# Seeed_XIAO_nRF52840_v1_0.net
KiCad netlist of a schematic drawn in EAGLE
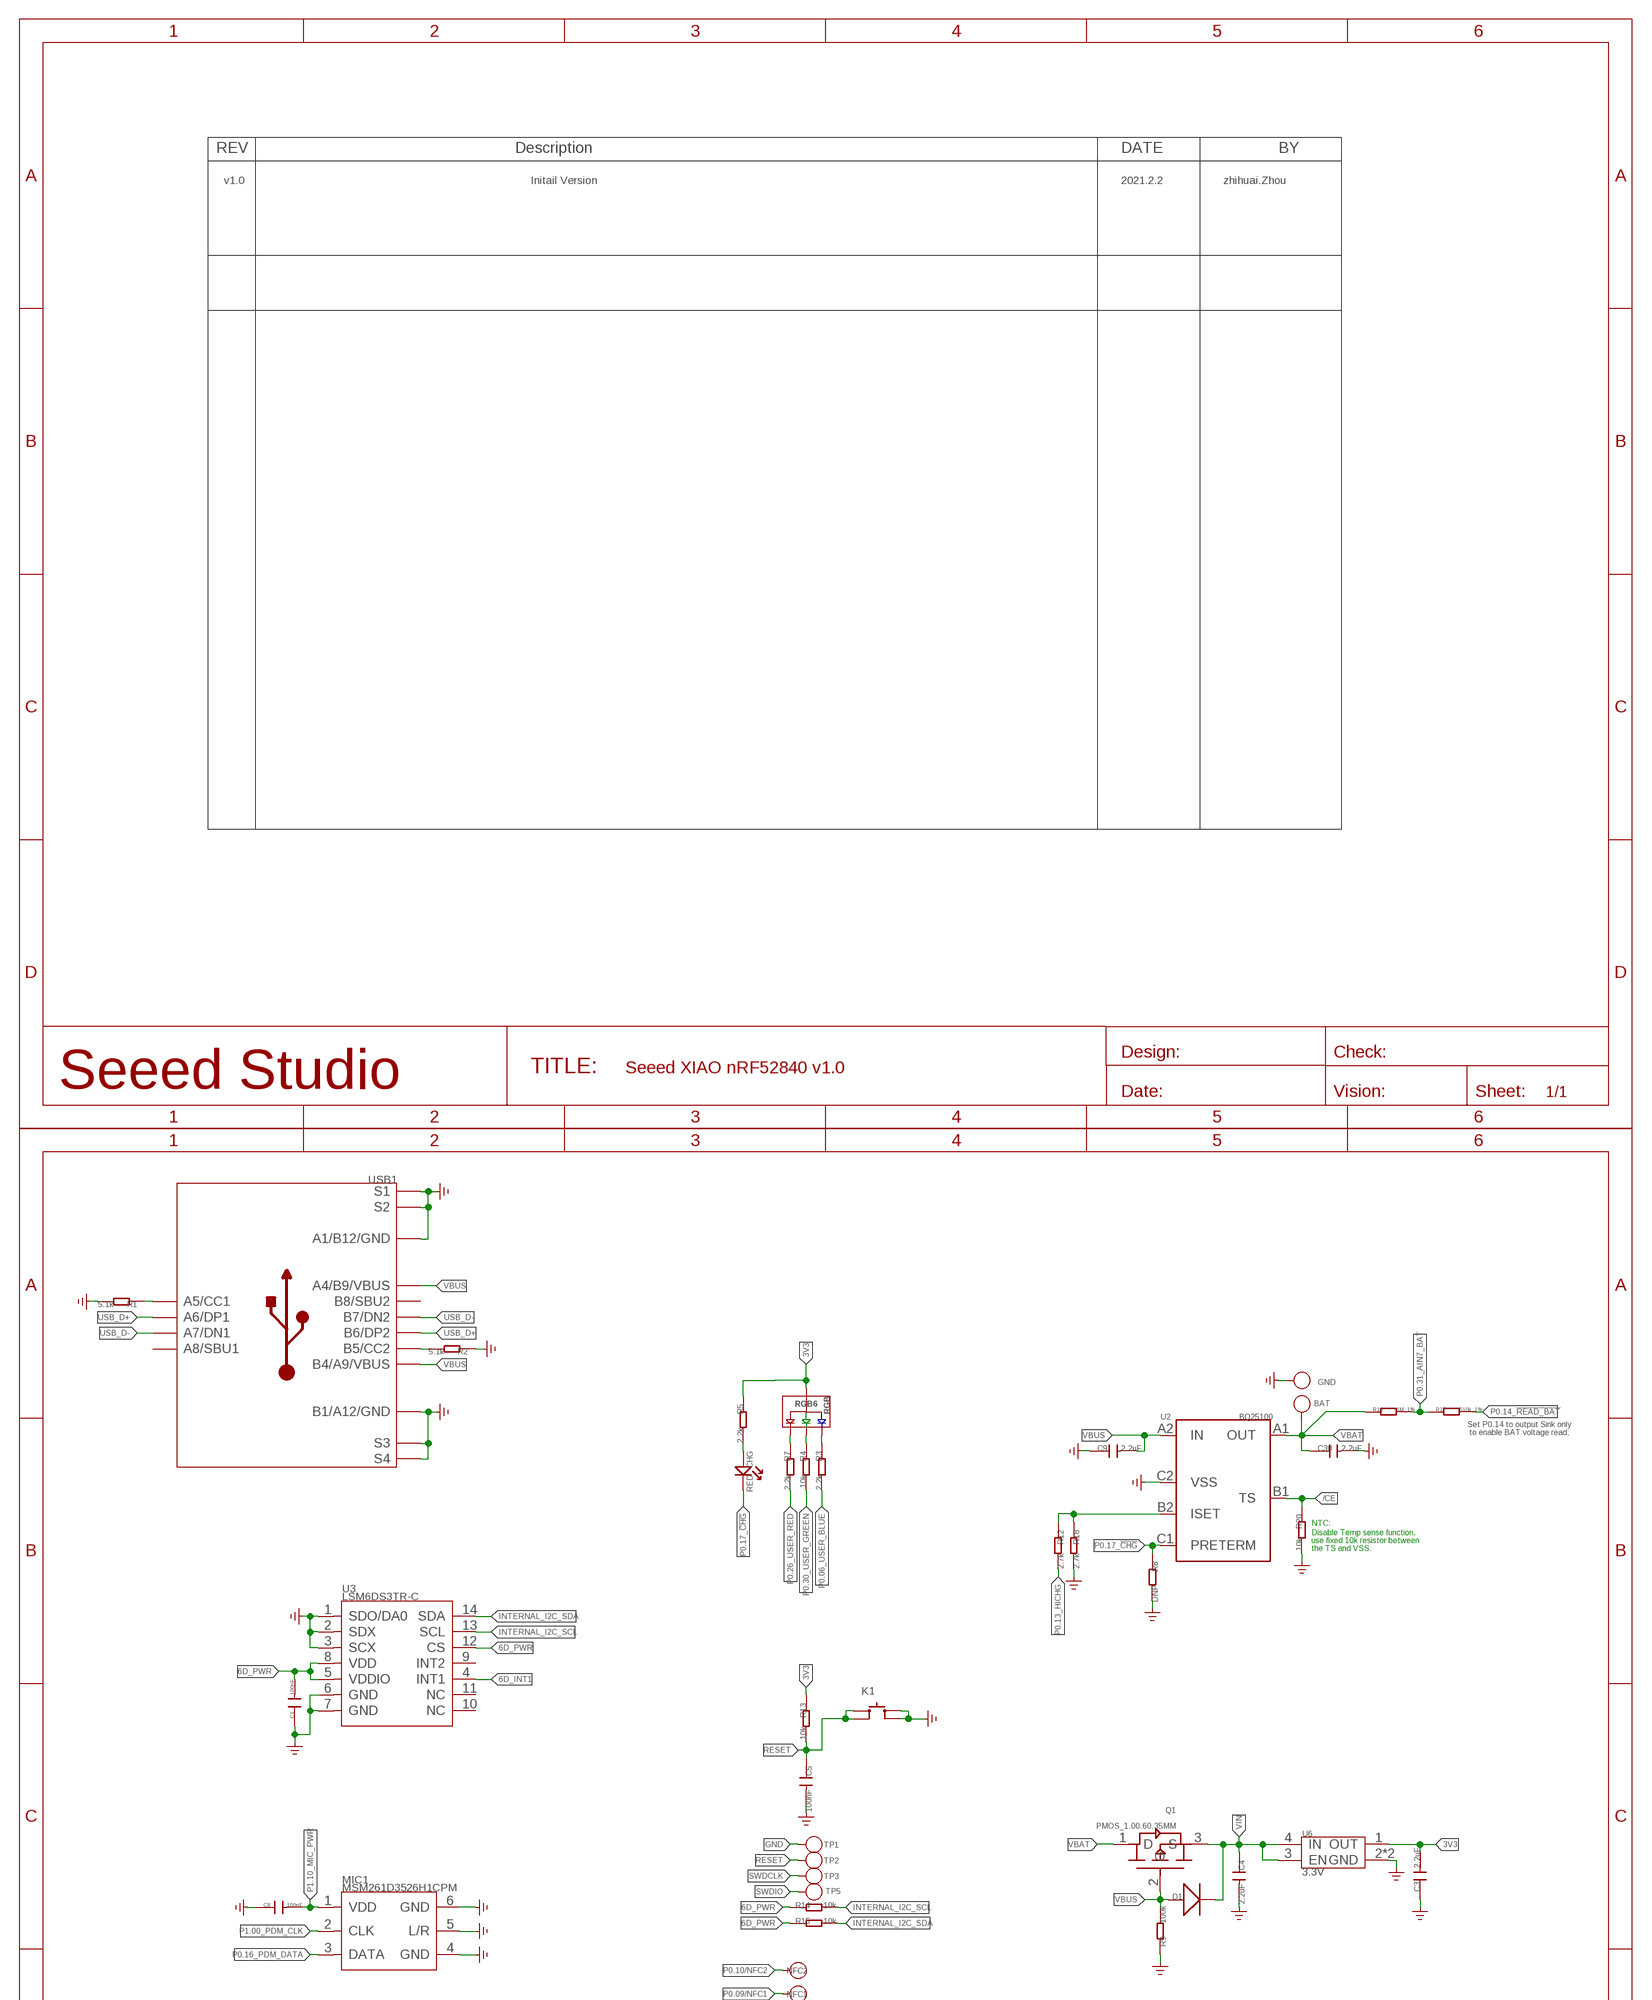
[diagram p0: schematic, sheet 1, part 1 of 2]
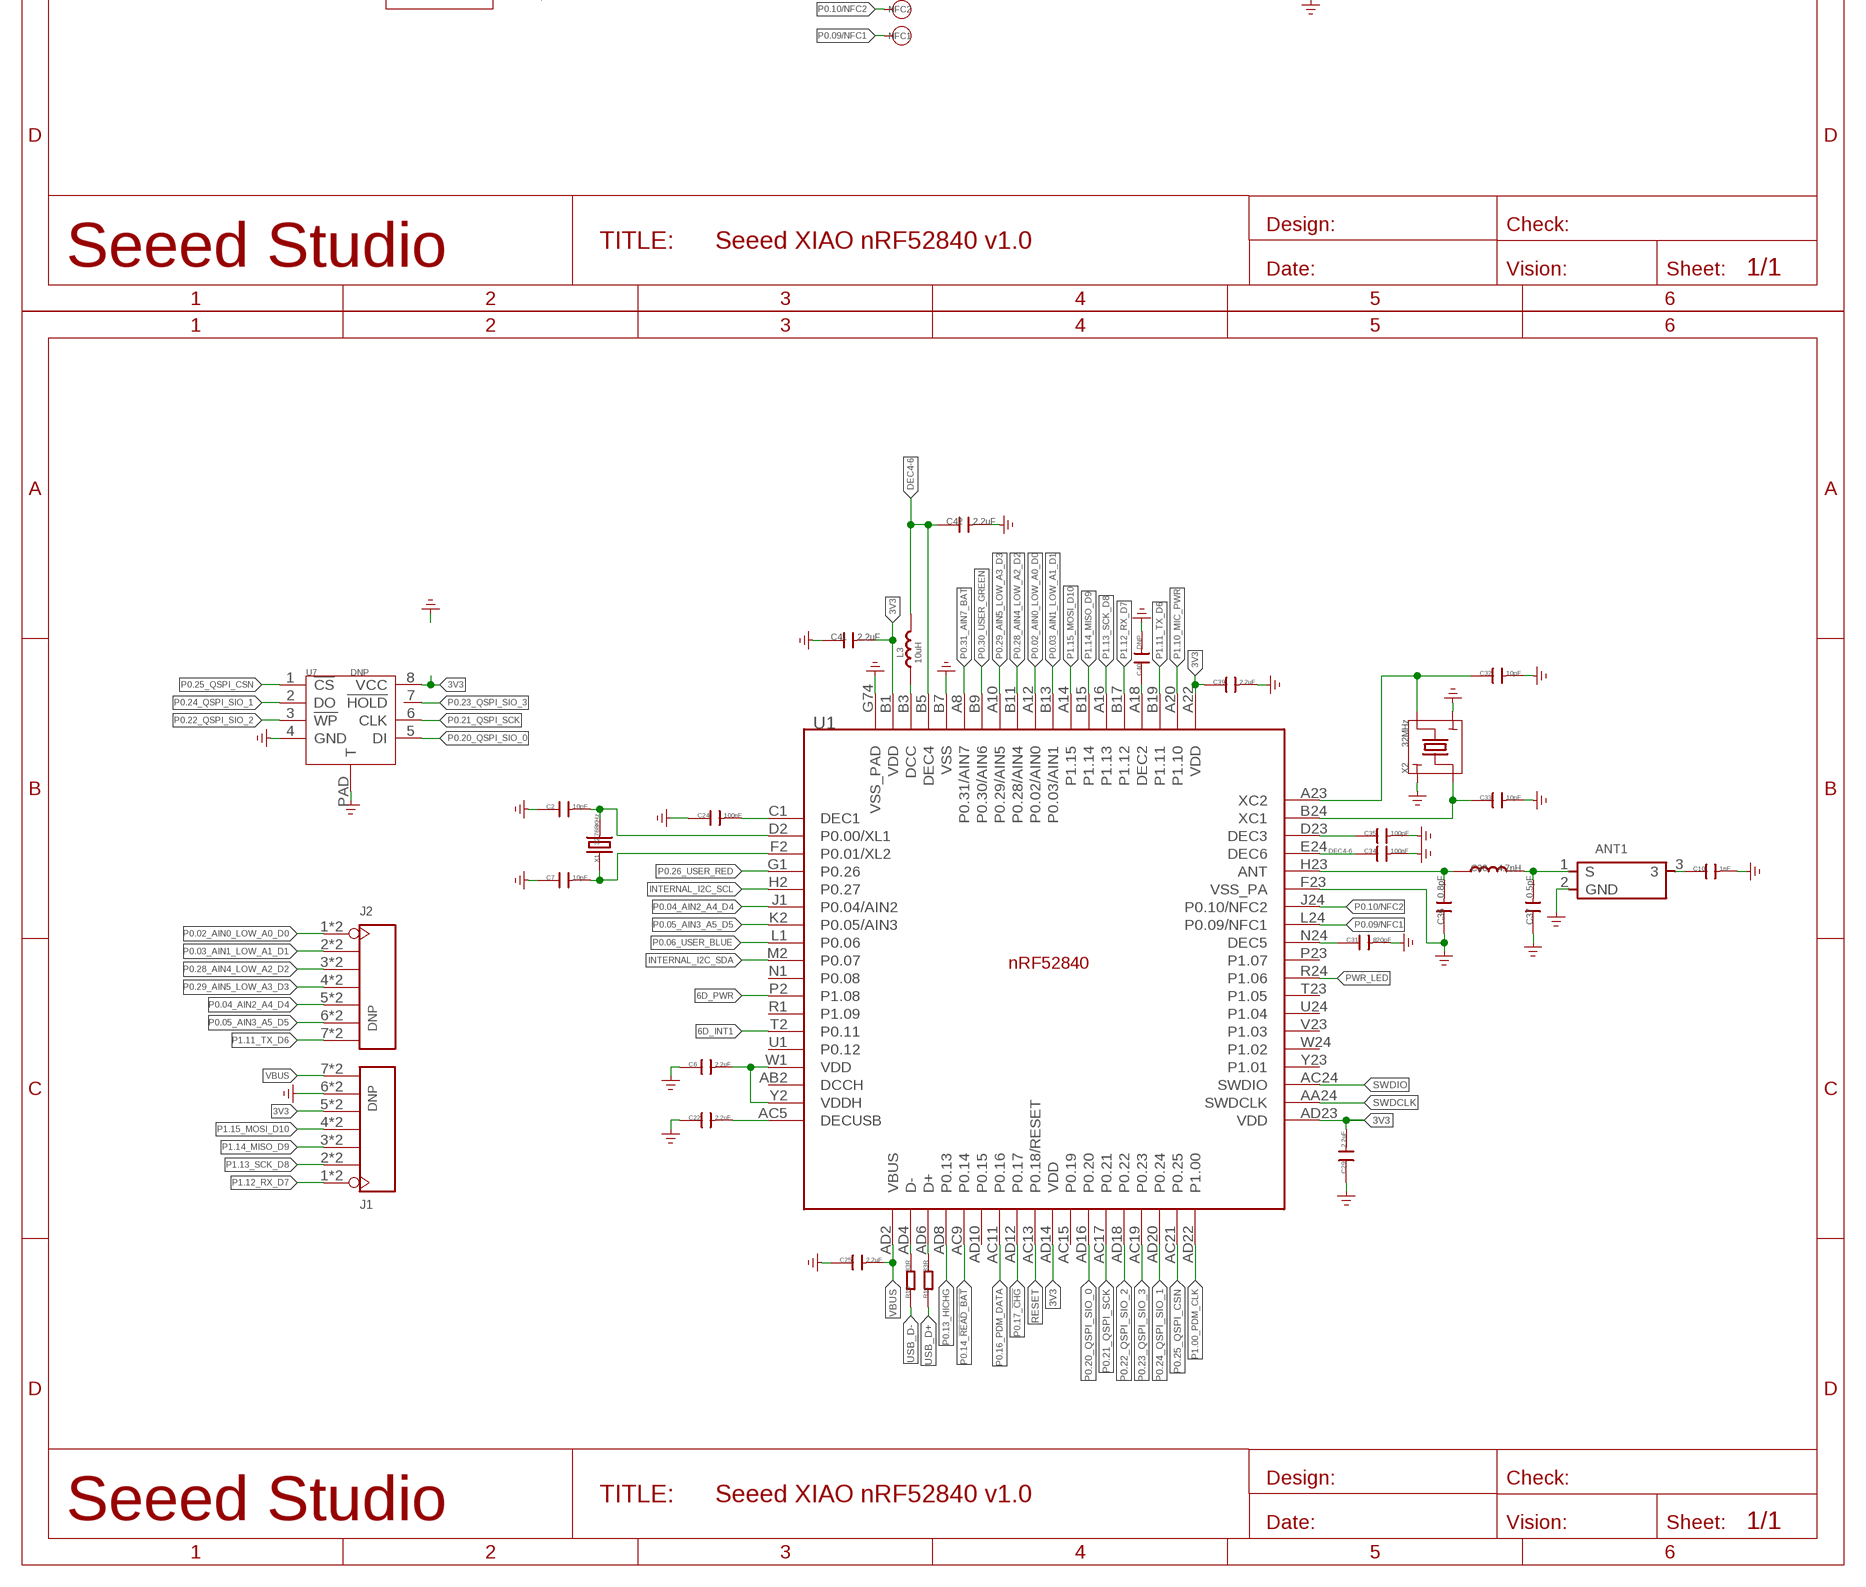
[diagram p1: schematic, sheet 1, part 2 of 2]

(export (version "E")
  (design (tool "Eeschema 10.0.6"))
  (components
    (comp (ref "ANT1")
      (value "ANTENNA-AN3216")
      (footprint "eagle-import:ANT-SMD3P-3.2X1.6X1.04MM")
      (libsource (lib "eagle-import") (part "ANTENNA-AN3216"))
    )
    (comp (ref "BAT")
      (value "TEST-POINT'4080'")
      (footprint "eagle-import:TP-80X40MIL")
      (libsource (lib "eagle-import") (part "TEST-POINT'4080'"))
    )
    (comp (ref "C1")
      (value "100nF")
      (footprint "eagle-import:C0201")
      (libsource (lib "eagle-import") (part "C-0201"))
    )
    (comp (ref "C2")
      (value "10pF")
      (footprint "eagle-import:C0201")
      (libsource (lib "eagle-import") (part "C-0201"))
    )
    (comp (ref "C3")
      (value "2.2uF")
      (footprint "eagle-import:C0201")
      (libsource (lib "eagle-import") (part "C-0201"))
    )
    (comp (ref "C4")
      (value "2.2uF")
      (footprint "eagle-import:C0201")
      (libsource (lib "eagle-import") (part "C-0201"))
    )
    (comp (ref "C5")
      (value "100nF")
      (footprint "eagle-import:C0201")
      (libsource (lib "eagle-import") (part "C-0201"))
    )
    (comp (ref "C6")
      (value "2.2uF")
      (footprint "eagle-import:C0201")
      (libsource (lib "eagle-import") (part "C-0201"))
    )
    (comp (ref "C7")
      (value "10pF")
      (footprint "eagle-import:C0201")
      (libsource (lib "eagle-import") (part "C-0201"))
    )
    (comp (ref "C8")
      (value "100nF")
      (footprint "eagle-import:C0201")
      (libsource (lib "eagle-import") (part "C-0201"))
    )
    (comp (ref "C9")
      (value "2.2uF")
      (footprint "eagle-import:C0201")
      (libsource (lib "eagle-import") (part "C-0201"))
    )
    (comp (ref "C10")
      (value "1nF")
      (footprint "eagle-import:C0402")
      (libsource (lib "eagle-import") (part "C-0402"))
    )
    (comp (ref "C22")
      (value "2.2uF")
      (footprint "eagle-import:C0201")
      (libsource (lib "eagle-import") (part "C-0201"))
    )
    (comp (ref "C24")
      (value "100nF")
      (footprint "eagle-import:C0201")
      (libsource (lib "eagle-import") (part "C-0201"))
    )
    (comp (ref "C25")
      (value "2.2uF")
      (footprint "eagle-import:C0201")
      (libsource (lib "eagle-import") (part "C-0201"))
    )
    (comp (ref "C29")
      (value "2.2uF")
      (footprint "eagle-import:C0201")
      (libsource (lib "eagle-import") (part "C-0201"))
    )
    (comp (ref "C30")
      (value "2.2uF")
      (footprint "eagle-import:C0201")
      (libsource (lib "eagle-import") (part "C-0201"))
    )
    (comp (ref "C31")
      (value "820pF")
      (footprint "eagle-import:C0201")
      (libsource (lib "eagle-import") (part "C-0201"))
    )
    (comp (ref "C32")
      (value "10pF")
      (footprint "eagle-import:C0201")
      (libsource (lib "eagle-import") (part "C-0201"))
    )
    (comp (ref "C33")
      (value "10pF")
      (footprint "eagle-import:C0201")
      (libsource (lib "eagle-import") (part "C-0201"))
    )
    (comp (ref "C34")
      (value "100nF")
      (footprint "eagle-import:C0201")
      (libsource (lib "eagle-import") (part "C-0201"))
    )
    (comp (ref "C35")
      (value "100pF")
      (footprint "eagle-import:C0201")
      (libsource (lib "eagle-import") (part "C-0201"))
    )
    (comp (ref "C36")
      (value "0.8pF")
      (footprint "eagle-import:C0201")
      (libsource (lib "eagle-import") (part "C-0201"))
    )
    (comp (ref "C37")
      (value "0.5pF")
      (footprint "eagle-import:C0201")
      (libsource (lib "eagle-import") (part "C-0201"))
    )
    (comp (ref "C38")
      (value "4.7nH")
      (footprint "eagle-import:L0201")
      (libsource (lib "eagle-import") (part "L0201"))
    )
    (comp (ref "C39")
      (value "2.2uF")
      (footprint "eagle-import:C0201")
      (libsource (lib "eagle-import") (part "C-0201"))
    )
    (comp (ref "C40")
      (value "DNP")
      (footprint "eagle-import:C0201")
      (libsource (lib "eagle-import") (part "C-0201"))
    )
    (comp (ref "C41")
      (value "2.2uF")
      (footprint "eagle-import:C0201")
      (libsource (lib "eagle-import") (part "C-0201"))
    )
    (comp (ref "C42")
      (value "2.2uF")
      (footprint "eagle-import:C0201")
      (libsource (lib "eagle-import") (part "C-0201"))
    )
    (comp (ref "CHG")
      (value "RED")
      (footprint "eagle-import:LED-0402")
      (libsource (lib "eagle-import") (part "LED-0402"))
    )
    (comp (ref "D1")
      (value "DIODE'0603'")
      (footprint "eagle-import:SOD-523")
      (libsource (lib "eagle-import") (part "DIODE'0603'"))
    )
    (comp (ref "GND")
      (value "GND")
      (footprint "eagle-import:TP-80X40MIL")
      (libsource (lib "eagle-import") (part "TEST-POINT'4080'"))
    )
    (comp (ref "J1")
      (value "DNP")
      (footprint "eagle-import:H7-HALF-HOLE-2.54")
      (libsource (lib "eagle-import") (part "HEADER-7P-HALF-HOLE-2.54"))
    )
    (comp (ref "J2")
      (value "DNP")
      (footprint "eagle-import:H7-HALF-HOLE-2.54")
      (libsource (lib "eagle-import") (part "HEADER-7P-HALF-HOLE-2.54"))
    )
    (comp (ref "K1")
      (value "BUTTON-4P")
      (footprint "eagle-import:SW4-SMD-2.8-2.6X1.6X0.53MM")
      (libsource (lib "eagle-import") (part "BUTTON-4P"))
    )
    (comp (ref "L3")
      (value "10uH")
      (footprint "eagle-import:L0603")
      (libsource (lib "eagle-import") (part "L0603"))
    )
    (comp (ref "MIC1")
      (value "MSM261D3526H1CPM")
      (footprint "eagle-import:MIC6P-3.5X2.65X0.94MM")
      (libsource (lib "eagle-import") (part "MIC-MSM261D3526H1CPM"))
    )
    (comp (ref "NFC1")
      (value "TEST-POINT'4080'")
      (footprint "eagle-import:TP-80X40MIL")
      (libsource (lib "eagle-import") (part "TEST-POINT'4080'"))
    )
    (comp (ref "NFC2")
      (value "TEST-POINT'4080'")
      (footprint "eagle-import:TP-80X40MIL")
      (libsource (lib "eagle-import") (part "TEST-POINT'4080'"))
    )
    (comp (ref "Q1")
      (value "PMOS_1.00.60.35MM")
      (footprint "eagle-import:PMOS_1.0_0.6_0.35MM")
      (libsource (lib "eagle-import") (part "PMOS_1.00.60.35MM"))
    )
    (comp (ref "R1")
      (value "5.1k")
      (footprint "eagle-import:R0201")
      (libsource (lib "eagle-import") (part "R-0201"))
    )
    (comp (ref "R2")
      (value "5.1k")
      (footprint "eagle-import:R0201")
      (libsource (lib "eagle-import") (part "R-0201"))
    )
    (comp (ref "R3")
      (value "2.2k")
      (footprint "eagle-import:R0201")
      (libsource (lib "eagle-import") (part "R-0201"))
    )
    (comp (ref "R4")
      (value "10k")
      (footprint "eagle-import:R0201")
      (libsource (lib "eagle-import") (part "R-0201"))
    )
    (comp (ref "R5")
      (value "2.2k")
      (footprint "eagle-import:R0201")
      (libsource (lib "eagle-import") (part "R-0201"))
    )
    (comp (ref "R7")
      (value "2.2k")
      (footprint "eagle-import:R0201")
      (libsource (lib "eagle-import") (part "R-0201"))
    )
    (comp (ref "R8")
      (value "DNP")
      (footprint "eagle-import:R0201")
      (libsource (lib "eagle-import") (part "R-0201"))
    )
    (comp (ref "R9")
      (value "100k")
      (footprint "eagle-import:R0201")
      (libsource (lib "eagle-import") (part "R-0201"))
    )
    (comp (ref "R10")
      (value "33R")
      (footprint "eagle-import:R0201")
      (libsource (lib "eagle-import") (part "R-0201"))
    )
    (comp (ref "R11")
      (value "33R")
      (footprint "eagle-import:R0201")
      (libsource (lib "eagle-import") (part "R-0201"))
    )
    (comp (ref "R12")
      (value "2.7k")
      (footprint "eagle-import:R0201")
      (libsource (lib "eagle-import") (part "R-0201"))
    )
    (comp (ref "R13")
      (value "10k")
      (footprint "eagle-import:R0201")
      (libsource (lib "eagle-import") (part "R-0201"))
    )
    (comp (ref "R14")
      (value "10k")
      (footprint "eagle-import:R0201")
      (libsource (lib "eagle-import") (part "R-0201"))
    )
    (comp (ref "R15")
      (value "10k")
      (footprint "eagle-import:R0201")
      (libsource (lib "eagle-import") (part "R-0201"))
    )
    (comp (ref "R16")
      (value "1M_1%")
      (footprint "eagle-import:R0201")
      (libsource (lib "eagle-import") (part "R-0201"))
    )
    (comp (ref "R17")
      (value "510k_1%")
      (footprint "eagle-import:R0201")
      (libsource (lib "eagle-import") (part "R-0201"))
    )
    (comp (ref "R18")
      (value "2.7k")
      (footprint "eagle-import:R0201")
      (libsource (lib "eagle-import") (part "R-0201"))
    )
    (comp (ref "R20")
      (value "10k")
      (footprint "eagle-import:R0201")
      (libsource (lib "eagle-import") (part "R-0201"))
    )
    (comp (ref "RGB6")
      (value "RGB")
      (footprint "eagle-import:4P1010")
      (libsource (lib "eagle-import") (part "RGB-1010"))
    )
    (comp (ref "TP1")
      (value "TEST-POINT'4545'")
      (footprint "eagle-import:TP-D45MIL")
      (fields (field (name "PARTNO") "DNP"))
      (libsource (lib "eagle-import") (part "TEST-POINT'4545'"))
    )
    (comp (ref "TP2")
      (value "TEST-POINT'4545'")
      (footprint "eagle-import:TP-D45MIL")
      (fields (field (name "PARTNO") "DNP"))
      (libsource (lib "eagle-import") (part "TEST-POINT'4545'"))
    )
    (comp (ref "TP3")
      (value "TEST-POINT'4545'")
      (footprint "eagle-import:TP-D45MIL")
      (fields (field (name "PARTNO") "DNP"))
      (libsource (lib "eagle-import") (part "TEST-POINT'4545'"))
    )
    (comp (ref "TP5")
      (value "TEST-POINT'4545'")
      (footprint "eagle-import:TP-D45MIL")
      (fields (field (name "PARTNO") "DNP"))
      (libsource (lib "eagle-import") (part "TEST-POINT'4545'"))
    )
    (comp (ref "U1")
      (value "NRF52840_QF")
      (footprint "eagle-import:AQFN50P700X700X85_HS-74N")
      (libsource (lib "eagle-import") (part "NRF52840_QF"))
    )
    (comp (ref "U2")
      (value "BQ25100")
      (footprint "eagle-import:BQ25101_DSBGA_6_BQ25101")
      (libsource (lib "eagle-import") (part "BQ25101_DSBGA_6_BQ25101_DSBGA_6"))
    )
    (comp (ref "U3")
      (value "LSM6DS3TR-C")
      (footprint "eagle-import:LGA14-0.5-2.5X3X0.86MM")
      (libsource (lib "eagle-import") (part "SENSOR-LSM6DS3TR-C"))
    )
    (comp (ref "U6")
      (value "3.3V")
      (footprint "eagle-import:X2SON-4")
      (libsource (lib "eagle-import") (part "TLV733P"))
    )
    (comp (ref "U7")
      (value "DNP")
      (footprint "eagle-import:USON2X3_8")
      (libsource (lib "eagle-import") (part "W25XXC"))
    )
    (comp (ref "USB1")
      (value "USB2.0-TYPE-C")
      (footprint "eagle-import:USB2.0-TYPE-C")
      (libsource (lib "eagle-import") (part "USB2.0-TYPE-C"))
    )
    (comp (ref "X1")
      (value "32.768KHz")
      (footprint "eagle-import:X2-SMD-L1.6X1.0X0.5MM")
      (libsource (lib "eagle-import") (part "CRYSTAL-2P-1610"))
    )
    (comp (ref "X2")
      (value "32MHz")
      (footprint "eagle-import:4P1612")
      (libsource (lib "eagle-import") (part "CRYSTAL'-1612'"))
    )
  )
  (nets
    (net (code "1") (name "/P0.14_~{READ_BAT}") (class "Default")
      (node (ref "R17") (pin "2") (pinfunction "2_2") (pintype "passive"))
      (node (ref "U1") (pin "AC9") (pinfunction "P0.14_AC9") (pintype "bidirectional"))
    )
    (net (code "2") (name "/P0.17_~{CHG}") (class "Default")
      (node (ref "CHG") (pin "-") (pinfunction "-_-") (pintype "passive"))
      (node (ref "R8") (pin "1") (pinfunction "1_1") (pintype "passive"))
      (node (ref "U1") (pin "AD12") (pinfunction "P0.17_AD12") (pintype "bidirectional"))
      (node (ref "U2") (pin "C1") (pinfunction "PRETERM_C1") (pintype "bidirectional"))
    )
    (net (code "3") (name "3V3") (class "Default")
      (node (ref "C29") (pin "2") (pinfunction "2_2") (pintype "passive"))
      (node (ref "C3") (pin "2") (pinfunction "2_2") (pintype "passive"))
      (node (ref "C39") (pin "1") (pinfunction "1_1") (pintype "passive"))
      (node (ref "C41") (pin "2") (pinfunction "2_2") (pintype "passive"))
      (node (ref "C6") (pin "2") (pinfunction "2_2") (pintype "passive"))
      (node (ref "J1") (pin "17") (pinfunction "5_17") (pintype "bidirectional"))
      (node (ref "J1") (pin "5") (pinfunction "5_5") (pintype "bidirectional"))
      (node (ref "R13") (pin "1") (pinfunction "1_1") (pintype "passive"))
      (node (ref "R5") (pin "1") (pinfunction "1_1") (pintype "passive"))
      (node (ref "RGB6") (pin "+") (pinfunction "+_+") (pintype "bidirectional"))
      (node (ref "U1") (pin "A22") (pinfunction "VDD_A22") (pintype "bidirectional"))
      (node (ref "U1") (pin "AD14") (pinfunction "VDD_AD14") (pintype "bidirectional"))
      (node (ref "U1") (pin "AD23") (pinfunction "VDD_AD23") (pintype "bidirectional"))
      (node (ref "U1") (pin "B1") (pinfunction "VDD_B1") (pintype "bidirectional"))
      (node (ref "U1") (pin "W1") (pinfunction "VDD_W1") (pintype "bidirectional"))
      (node (ref "U1") (pin "Y2") (pinfunction "VDDH_Y2") (pintype "bidirectional"))
      (node (ref "U6") (pin "1") (pinfunction "OUT_1") (pintype "bidirectional"))
      (node (ref "U7") (pin "8") (pinfunction "VCC_8") (pintype "bidirectional"))
    )
    (net (code "4") (name "6D_INT1") (class "Default")
      (node (ref "U1") (pin "T2") (pinfunction "P0.11_T2") (pintype "bidirectional"))
      (node (ref "U3") (pin "4") (pinfunction "INT1_4") (pintype "bidirectional"))
    )
    (net (code "5") (name "6D_PWR") (class "Default")
      (node (ref "C1") (pin "2") (pinfunction "2_2") (pintype "passive"))
      (node (ref "R14") (pin "1") (pinfunction "1_1") (pintype "passive"))
      (node (ref "R15") (pin "1") (pinfunction "1_1") (pintype "passive"))
      (node (ref "U1") (pin "P2") (pinfunction "P1.08_P2") (pintype "bidirectional"))
      (node (ref "U3") (pin "12") (pinfunction "CS_12") (pintype "bidirectional"))
      (node (ref "U3") (pin "5") (pinfunction "VDDIO_5") (pintype "bidirectional"))
      (node (ref "U3") (pin "8") (pinfunction "VDD_8") (pintype "bidirectional"))
    )
    (net (code "6") (name "DEC4-6") (class "Default")
      (node (ref "C34") (pin "1") (pinfunction "1_1") (pintype "passive"))
      (node (ref "C42") (pin "1") (pinfunction "1_1") (pintype "passive"))
      (node (ref "L3") (pin "2") (pinfunction "2_2") (pintype "passive"))
      (node (ref "U1") (pin "B5") (pinfunction "DEC4_B5") (pintype "bidirectional"))
      (node (ref "U1") (pin "E24") (pinfunction "DEC6_E24") (pintype "bidirectional"))
    )
    (net (code "7") (name "GND") (class "Default")
      (node (ref "ANT1") (pin "2") (pinfunction "GND_2") (pintype "bidirectional"))
      (node (ref "C1") (pin "1") (pinfunction "1_1") (pintype "passive"))
      (node (ref "C10") (pin "2") (pinfunction "2_2") (pintype "passive"))
      (node (ref "C2") (pin "1") (pinfunction "1_1") (pintype "passive"))
      (node (ref "C22") (pin "1") (pinfunction "1_1") (pintype "passive"))
      (node (ref "C24") (pin "1") (pinfunction "1_1") (pintype "passive"))
      (node (ref "C25") (pin "1") (pinfunction "1_1") (pintype "passive"))
      (node (ref "C29") (pin "1") (pinfunction "1_1") (pintype "passive"))
      (node (ref "C3") (pin "1") (pinfunction "1_1") (pintype "passive"))
      (node (ref "C30") (pin "2") (pinfunction "2_2") (pintype "passive"))
      (node (ref "C31") (pin "2") (pinfunction "2_2") (pintype "passive"))
      (node (ref "C32") (pin "2") (pinfunction "2_2") (pintype "passive"))
      (node (ref "C33") (pin "2") (pinfunction "2_2") (pintype "passive"))
      (node (ref "C34") (pin "2") (pinfunction "2_2") (pintype "passive"))
      (node (ref "C35") (pin "2") (pinfunction "2_2") (pintype "passive"))
      (node (ref "C36") (pin "1") (pinfunction "1_1") (pintype "passive"))
      (node (ref "C37") (pin "1") (pinfunction "1_1") (pintype "passive"))
      (node (ref "C39") (pin "2") (pinfunction "2_2") (pintype "passive"))
      (node (ref "C4") (pin "2") (pinfunction "2_2") (pintype "passive"))
      (node (ref "C40") (pin "2") (pinfunction "2_2") (pintype "passive"))
      (node (ref "C41") (pin "1") (pinfunction "1_1") (pintype "passive"))
      (node (ref "C42") (pin "2") (pinfunction "2_2") (pintype "passive"))
      (node (ref "C5") (pin "2") (pinfunction "2_2") (pintype "passive"))
      (node (ref "C6") (pin "1") (pinfunction "1_1") (pintype "passive"))
      (node (ref "C7") (pin "1") (pinfunction "1_1") (pintype "passive"))
      (node (ref "C8") (pin "1") (pinfunction "1_1") (pintype "passive"))
      (node (ref "C9") (pin "1") (pinfunction "1_1") (pintype "passive"))
      (node (ref "GND") (pin "1") (pinfunction "T_1") (pintype "bidirectional"))
      (node (ref "J1") (pin "18") (pinfunction "6_18") (pintype "bidirectional"))
      (node (ref "J1") (pin "6") (pinfunction "6_6") (pintype "bidirectional"))
      (node (ref "K1") (pin "2") (pinfunction "B0_2") (pintype "bidirectional"))
      (node (ref "K1") (pin "4") (pinfunction "B1_4") (pintype "bidirectional"))
      (node (ref "MIC1") (pin "4") (pinfunction "GND_4") (pintype "bidirectional"))
      (node (ref "MIC1") (pin "5") (pinfunction "L/R_5") (pintype "bidirectional"))
      (node (ref "MIC1") (pin "6") (pinfunction "GND_6") (pintype "bidirectional"))
      (node (ref "R1") (pin "2") (pinfunction "2_2") (pintype "passive"))
      (node (ref "R18") (pin "2") (pinfunction "2_2") (pintype "passive"))
      (node (ref "R2") (pin "1") (pinfunction "1_1") (pintype "passive"))
      (node (ref "R20") (pin "2") (pinfunction "2_2") (pintype "passive"))
      (node (ref "R8") (pin "2") (pinfunction "2_2") (pintype "passive"))
      (node (ref "R9") (pin "1") (pinfunction "1_1") (pintype "passive"))
      (node (ref "TP1") (pin "T") (pinfunction "T_T") (pintype "bidirectional"))
      (node (ref "U1") (pin "B7") (pinfunction "VSS_B7") (pintype "bidirectional"))
      (node (ref "U1") (pin "F23") (pinfunction "VSS_PA_F23") (pintype "bidirectional"))
      (node (ref "U1") (pin "G74") (pinfunction "VSS_PAD_G74") (pintype "bidirectional"))
      (node (ref "U2") (pin "C2") (pinfunction "VSS_C2") (pintype "bidirectional"))
      (node (ref "U3") (pin "1") (pinfunction "SDO/DA0_1") (pintype "bidirectional"))
      (node (ref "U3") (pin "2") (pinfunction "SDX_2") (pintype "bidirectional"))
      (node (ref "U3") (pin "3") (pinfunction "SCX_3") (pintype "bidirectional"))
      (node (ref "U3") (pin "6") (pinfunction "GND_6") (pintype "bidirectional"))
      (node (ref "U3") (pin "7") (pinfunction "GND_7") (pintype "bidirectional"))
      (node (ref "U6") (pin "2") (pinfunction "GND_2") (pintype "bidirectional"))
      (node (ref "U6") (pin "T") (pinfunction "GND_T") (pintype "bidirectional"))
      (node (ref "U7") (pin "4") (pinfunction "GND_4") (pintype "bidirectional"))
      (node (ref "U7") (pin "PAD") (pinfunction "T_PAD") (pintype "bidirectional"))
      (node (ref "USB1") (pin "A1_B12") (pinfunction "A1/B12/GND_A1_B12") (pintype "bidirectional"))
      (node (ref "USB1") (pin "B1_A12") (pinfunction "B1/A12/GND_B1_A12") (pintype "bidirectional"))
      (node (ref "USB1") (pin "S1") (pinfunction "S1_S1") (pintype "bidirectional"))
      (node (ref "USB1") (pin "S2") (pinfunction "S2_S2") (pintype "bidirectional"))
      (node (ref "USB1") (pin "S3") (pinfunction "S3_S3") (pintype "bidirectional"))
      (node (ref "USB1") (pin "S4") (pinfunction "S4_S4") (pintype "bidirectional"))
      (node (ref "USB1") (pin "S5") (pinfunction "S1_S5") (pintype "bidirectional"))
      (node (ref "USB1") (pin "S6") (pinfunction "S2_S6") (pintype "bidirectional"))
      (node (ref "X2") (pin "2") (pinfunction "1_2") (pintype "bidirectional"))
      (node (ref "X2") (pin "4") (pinfunction "3_4") (pintype "bidirectional"))
    )
    (net (code "8") (name "INTERNAL_I2C_SCL") (class "Default")
      (node (ref "R14") (pin "2") (pinfunction "2_2") (pintype "passive"))
      (node (ref "U1") (pin "H2") (pinfunction "P0.27_H2") (pintype "bidirectional"))
      (node (ref "U3") (pin "13") (pinfunction "SCL_13") (pintype "bidirectional"))
    )
    (net (code "9") (name "INTERNAL_I2C_SDA") (class "Default")
      (node (ref "R15") (pin "2") (pinfunction "2_2") (pintype "passive"))
      (node (ref "U1") (pin "M2") (pinfunction "P0.07_M2") (pintype "bidirectional"))
      (node (ref "U3") (pin "14") (pinfunction "SDA_14") (pintype "bidirectional"))
    )
    (net (code "10") (name "Net-(ANT1-Pad3)") (class "Default")
      (node (ref "ANT1") (pin "3") (pinfunction "3_3") (pintype "bidirectional"))
      (node (ref "C10") (pin "1") (pinfunction "1_1") (pintype "passive"))
    )
    (net (code "11") (name "Net-(ANT1-S)") (class "Default")
      (node (ref "ANT1") (pin "1") (pinfunction "S_1") (pintype "bidirectional"))
      (node (ref "C37") (pin "2") (pinfunction "2_2") (pintype "passive"))
      (node (ref "C38") (pin "2") (pinfunction "2_2") (pintype "passive"))
    )
    (net (code "12") (name "Net-(CHG-Pad+)") (class "Default")
      (node (ref "CHG") (pin "+") (pinfunction "+_+") (pintype "passive"))
      (node (ref "R5") (pin "2") (pinfunction "2_2") (pintype "passive"))
    )
    (net (code "13") (name "Net-(R3-Pad1)") (class "Default")
      (node (ref "R3") (pin "1") (pinfunction "1_1") (pintype "passive"))
      (node (ref "RGB6") (pin "B-") (pinfunction "B-_B-") (pintype "bidirectional"))
    )
    (net (code "14") (name "Net-(R4-Pad1)") (class "Default")
      (node (ref "R4") (pin "1") (pinfunction "1_1") (pintype "passive"))
      (node (ref "RGB6") (pin "G-") (pinfunction "G-_G-") (pintype "bidirectional"))
    )
    (net (code "15") (name "Net-(R7-Pad1)") (class "Default")
      (node (ref "R7") (pin "1") (pinfunction "1_1") (pintype "passive"))
      (node (ref "RGB6") (pin "R-") (pinfunction "R-_R-") (pintype "bidirectional"))
    )
    (net (code "16") (name "Net-(U1-ANT)") (class "Default")
      (node (ref "C36") (pin "2") (pinfunction "2_2") (pintype "passive"))
      (node (ref "C38") (pin "1") (pinfunction "1_1") (pintype "passive"))
      (node (ref "U1") (pin "H23") (pinfunction "ANT_H23") (pintype "bidirectional"))
    )
    (net (code "17") (name "Net-(U1-D+)") (class "Default")
      (node (ref "R11") (pin "2") (pinfunction "2_2") (pintype "passive"))
      (node (ref "U1") (pin "AD6") (pinfunction "D+_AD6") (pintype "bidirectional"))
    )
    (net (code "18") (name "Net-(U1-D-)") (class "Default")
      (node (ref "R10") (pin "2") (pinfunction "2_2") (pintype "passive"))
      (node (ref "U1") (pin "AD4") (pinfunction "D-_AD4") (pintype "bidirectional"))
    )
    (net (code "19") (name "Net-(U1-DCC)") (class "Default")
      (node (ref "L3") (pin "1") (pinfunction "1_1") (pintype "passive"))
      (node (ref "U1") (pin "B3") (pinfunction "DCC_B3") (pintype "bidirectional"))
    )
    (net (code "20") (name "Net-(U1-DEC1)") (class "Default")
      (node (ref "C24") (pin "2") (pinfunction "2_2") (pintype "passive"))
      (node (ref "U1") (pin "C1") (pinfunction "DEC1_C1") (pintype "bidirectional"))
    )
    (net (code "21") (name "Net-(U1-DEC2)") (class "Default")
      (node (ref "C40") (pin "1") (pinfunction "1_1") (pintype "passive"))
      (node (ref "U1") (pin "A18") (pinfunction "DEC2_A18") (pintype "bidirectional"))
    )
    (net (code "22") (name "Net-(U1-DEC3)") (class "Default")
      (node (ref "C35") (pin "1") (pinfunction "1_1") (pintype "passive"))
      (node (ref "U1") (pin "D23") (pinfunction "DEC3_D23") (pintype "bidirectional"))
    )
    (net (code "23") (name "Net-(U1-DEC5)") (class "Default")
      (node (ref "C31") (pin "1") (pinfunction "1_1") (pintype "passive"))
      (node (ref "U1") (pin "N24") (pinfunction "DEC5_N24") (pintype "bidirectional"))
    )
    (net (code "24") (name "Net-(U1-DECUSB)") (class "Default")
      (node (ref "C22") (pin "2") (pinfunction "2_2") (pintype "passive"))
      (node (ref "U1") (pin "AC5") (pinfunction "DECUSB_AC5") (pintype "bidirectional"))
    )
    (net (code "25") (name "Net-(U1-P0.00{slash}XL1)") (class "Default")
      (node (ref "C2") (pin "2") (pinfunction "2_2") (pintype "passive"))
      (node (ref "U1") (pin "D2") (pinfunction "P0.00/XL1_D2") (pintype "bidirectional"))
      (node (ref "X1") (pin "2") (pinfunction "2_2") (pintype "passive"))
    )
    (net (code "26") (name "Net-(U1-P0.01{slash}XL2)") (class "Default")
      (node (ref "C7") (pin "2") (pinfunction "2_2") (pintype "passive"))
      (node (ref "U1") (pin "F2") (pinfunction "P0.01/XL2_F2") (pintype "bidirectional"))
      (node (ref "X1") (pin "1") (pinfunction "1_1") (pintype "passive"))
    )
    (net (code "27") (name "Net-(U1-XC1)") (class "Default")
      (node (ref "C33") (pin "1") (pinfunction "1_1") (pintype "passive"))
      (node (ref "U1") (pin "B24") (pinfunction "XC1_B24") (pintype "bidirectional"))
      (node (ref "X2") (pin "1") (pinfunction "2_1") (pintype "passive"))
    )
    (net (code "28") (name "Net-(U1-XC2)") (class "Default")
      (node (ref "C32") (pin "1") (pinfunction "1_1") (pintype "passive"))
      (node (ref "U1") (pin "A23") (pinfunction "XC2_A23") (pintype "bidirectional"))
      (node (ref "X2") (pin "3") (pinfunction "4_3") (pintype "passive"))
    )
    (net (code "29") (name "Net-(U2-ISET)") (class "Default")
      (node (ref "R12") (pin "1") (pinfunction "1_1") (pintype "passive"))
      (node (ref "R18") (pin "1") (pinfunction "1_1") (pintype "passive"))
      (node (ref "U2") (pin "B2") (pinfunction "ISET_B2") (pintype "bidirectional"))
    )
    (net (code "30") (name "Net-(USB1-A5{slash}CC1)") (class "Default")
      (node (ref "R1") (pin "1") (pinfunction "1_1") (pintype "passive"))
      (node (ref "USB1") (pin "A5") (pinfunction "A5/CC1_A5") (pintype "bidirectional"))
    )
    (net (code "31") (name "Net-(USB1-B5{slash}CC2)") (class "Default")
      (node (ref "R2") (pin "2") (pinfunction "2_2") (pintype "passive"))
      (node (ref "USB1") (pin "B5") (pinfunction "B5/CC2_B5") (pintype "bidirectional"))
    )
    (net (code "32") (name "P0.02_AIN0_LOW_A0_D0") (class "Default")
      (node (ref "J2") (pin "1") (pinfunction "1_1") (pintype "bidirectional"))
      (node (ref "J2") (pin "13") (pinfunction "1_13") (pintype "bidirectional"))
      (node (ref "U1") (pin "A12") (pinfunction "P0.02/AIN0_A12") (pintype "bidirectional"))
    )
    (net (code "33") (name "P0.03_AIN1_LOW_A1_D1") (class "Default")
      (node (ref "J2") (pin "14") (pinfunction "2_14") (pintype "bidirectional"))
      (node (ref "J2") (pin "2") (pinfunction "2_2") (pintype "bidirectional"))
      (node (ref "U1") (pin "B13") (pinfunction "P0.03/AIN1_B13") (pintype "bidirectional"))
    )
    (net (code "34") (name "P0.04_AIN2_A4_D4") (class "Default")
      (node (ref "J2") (pin "17") (pinfunction "5_17") (pintype "bidirectional"))
      (node (ref "J2") (pin "5") (pinfunction "5_5") (pintype "bidirectional"))
      (node (ref "U1") (pin "J1") (pinfunction "P0.04/AIN2_J1") (pintype "bidirectional"))
    )
    (net (code "35") (name "P0.05_AIN3_A5_D5") (class "Default")
      (node (ref "J2") (pin "18") (pinfunction "6_18") (pintype "bidirectional"))
      (node (ref "J2") (pin "6") (pinfunction "6_6") (pintype "bidirectional"))
      (node (ref "U1") (pin "K2") (pinfunction "P0.05/AIN3_K2") (pintype "bidirectional"))
    )
    (net (code "36") (name "P0.06_USER_BLUE") (class "Default")
      (node (ref "R3") (pin "2") (pinfunction "2_2") (pintype "passive"))
      (node (ref "U1") (pin "L1") (pinfunction "P0.06_L1") (pintype "bidirectional"))
    )
    (net (code "37") (name "P0.09{slash}NFC1") (class "Default")
      (node (ref "NFC1") (pin "1") (pinfunction "T_1") (pintype "bidirectional"))
      (node (ref "U1") (pin "L24") (pinfunction "P0.09/NFC1_L24") (pintype "bidirectional"))
    )
    (net (code "38") (name "P0.10{slash}NFC2") (class "Default")
      (node (ref "NFC2") (pin "1") (pinfunction "T_1") (pintype "bidirectional"))
      (node (ref "U1") (pin "J24") (pinfunction "P0.10/NFC2_J24") (pintype "bidirectional"))
    )
    (net (code "39") (name "P0.13_HICHG") (class "Default")
      (node (ref "R12") (pin "2") (pinfunction "2_2") (pintype "passive"))
      (node (ref "U1") (pin "AD8") (pinfunction "P0.13_AD8") (pintype "bidirectional"))
    )
    (net (code "40") (name "P0.16_PDM_DATA") (class "Default")
      (node (ref "MIC1") (pin "3") (pinfunction "DATA_3") (pintype "bidirectional"))
      (node (ref "U1") (pin "AC11") (pinfunction "P0.16_AC11") (pintype "bidirectional"))
    )
    (net (code "41") (name "P0.20_QSPI_SIO_0") (class "Default")
      (node (ref "U1") (pin "AD16") (pinfunction "P0.20_AD16") (pintype "bidirectional"))
      (node (ref "U7") (pin "5") (pinfunction "DI_5") (pintype "bidirectional"))
    )
    (net (code "42") (name "P0.21_QSPI_SCK") (class "Default")
      (node (ref "U1") (pin "AC17") (pinfunction "P0.21_AC17") (pintype "bidirectional"))
      (node (ref "U7") (pin "6") (pinfunction "CLK_6") (pintype "bidirectional"))
    )
    (net (code "43") (name "P0.22_QSPI_SIO_2") (class "Default")
      (node (ref "U1") (pin "AD18") (pinfunction "P0.22_AD18") (pintype "bidirectional"))
      (node (ref "U7") (pin "3") (pinfunction "~{WP}_3") (pintype "bidirectional"))
    )
    (net (code "44") (name "P0.23_QSPI_SIO_3") (class "Default")
      (node (ref "U1") (pin "AC19") (pinfunction "P0.23_AC19") (pintype "bidirectional"))
      (node (ref "U7") (pin "7") (pinfunction "~{HOLD}_7") (pintype "bidirectional"))
    )
    (net (code "45") (name "P0.24_QSPI_SIO_1") (class "Default")
      (node (ref "U1") (pin "AD20") (pinfunction "P0.24_AD20") (pintype "bidirectional"))
      (node (ref "U7") (pin "2") (pinfunction "DO_2") (pintype "bidirectional"))
    )
    (net (code "46") (name "P0.25_QSPI_CSN") (class "Default")
      (node (ref "U1") (pin "AC21") (pinfunction "P0.25_AC21") (pintype "bidirectional"))
      (node (ref "U7") (pin "1") (pinfunction "~{CS}_1") (pintype "bidirectional"))
    )
    (net (code "47") (name "P0.26_USER_RED") (class "Default")
      (node (ref "R7") (pin "2") (pinfunction "2_2") (pintype "passive"))
      (node (ref "U1") (pin "G1") (pinfunction "P0.26_G1") (pintype "bidirectional"))
    )
    (net (code "48") (name "P0.28_AIN4_LOW_A2_D2") (class "Default")
      (node (ref "J2") (pin "15") (pinfunction "3_15") (pintype "bidirectional"))
      (node (ref "J2") (pin "3") (pinfunction "3_3") (pintype "bidirectional"))
      (node (ref "U1") (pin "B11") (pinfunction "P0.28/AIN4_B11") (pintype "bidirectional"))
    )
    (net (code "49") (name "P0.29_AIN5_LOW_A3_D3") (class "Default")
      (node (ref "J2") (pin "16") (pinfunction "4_16") (pintype "bidirectional"))
      (node (ref "J2") (pin "4") (pinfunction "4_4") (pintype "bidirectional"))
      (node (ref "U1") (pin "A10") (pinfunction "P0.29/AIN5_A10") (pintype "bidirectional"))
    )
    (net (code "50") (name "P0.30_USER_GREEN") (class "Default")
      (node (ref "R4") (pin "2") (pinfunction "2_2") (pintype "passive"))
      (node (ref "U1") (pin "B9") (pinfunction "P0.30/AIN6_B9") (pintype "bidirectional"))
    )
    (net (code "51") (name "P0.31_AIN7_BAT") (class "Default")
      (node (ref "R16") (pin "2") (pinfunction "2_2") (pintype "passive"))
      (node (ref "R17") (pin "1") (pinfunction "1_1") (pintype "passive"))
      (node (ref "U1") (pin "A8") (pinfunction "P0.31/AIN7_A8") (pintype "bidirectional"))
    )
    (net (code "52") (name "P1.00_PDM_CLK") (class "Default")
      (node (ref "MIC1") (pin "2") (pinfunction "CLK_2") (pintype "bidirectional"))
      (node (ref "U1") (pin "AD22") (pinfunction "P1.00_AD22") (pintype "bidirectional"))
    )
    (net (code "53") (name "P1.10_MIC_PWR") (class "Default")
      (node (ref "C8") (pin "2") (pinfunction "2_2") (pintype "passive"))
      (node (ref "MIC1") (pin "1") (pinfunction "VDD_1") (pintype "bidirectional"))
      (node (ref "U1") (pin "A20") (pinfunction "P1.10_A20") (pintype "bidirectional"))
    )
    (net (code "54") (name "P1.11_TX_D6") (class "Default")
      (node (ref "J2") (pin "19") (pinfunction "7_19") (pintype "bidirectional"))
      (node (ref "J2") (pin "7") (pinfunction "7_7") (pintype "bidirectional"))
      (node (ref "U1") (pin "B19") (pinfunction "P1.11_B19") (pintype "bidirectional"))
    )
    (net (code "55") (name "P1.12_RX_D7") (class "Default")
      (node (ref "J1") (pin "1") (pinfunction "1_1") (pintype "bidirectional"))
      (node (ref "J1") (pin "13") (pinfunction "1_13") (pintype "bidirectional"))
      (node (ref "U1") (pin "B17") (pinfunction "P1.12_B17") (pintype "bidirectional"))
    )
    (net (code "56") (name "P1.13_SCK_D8") (class "Default")
      (node (ref "J1") (pin "14") (pinfunction "2_14") (pintype "bidirectional"))
      (node (ref "J1") (pin "2") (pinfunction "2_2") (pintype "bidirectional"))
      (node (ref "U1") (pin "A16") (pinfunction "P1.13_A16") (pintype "bidirectional"))
    )
    (net (code "57") (name "P1.14_MISO_D9") (class "Default")
      (node (ref "J1") (pin "15") (pinfunction "3_15") (pintype "bidirectional"))
      (node (ref "J1") (pin "3") (pinfunction "3_3") (pintype "bidirectional"))
      (node (ref "U1") (pin "B15") (pinfunction "P1.14_B15") (pintype "bidirectional"))
    )
    (net (code "58") (name "P1.15_MOSI_D10") (class "Default")
      (node (ref "J1") (pin "16") (pinfunction "4_16") (pintype "bidirectional"))
      (node (ref "J1") (pin "4") (pinfunction "4_4") (pintype "bidirectional"))
      (node (ref "U1") (pin "A14") (pinfunction "P1.15_A14") (pintype "bidirectional"))
    )
    (net (code "59") (name "PWR_LED") (class "Default")
      (node (ref "U1") (pin "R24") (pinfunction "P1.06_R24") (pintype "bidirectional"))
    )
    (net (code "60") (name "RESET") (class "Default")
      (node (ref "C5") (pin "1") (pinfunction "1_1") (pintype "passive"))
      (node (ref "K1") (pin "1") (pinfunction "A0_1") (pintype "bidirectional"))
      (node (ref "K1") (pin "3") (pinfunction "A1_3") (pintype "bidirectional"))
      (node (ref "R13") (pin "2") (pinfunction "2_2") (pintype "passive"))
      (node (ref "TP2") (pin "T") (pinfunction "T_T") (pintype "bidirectional"))
      (node (ref "U1") (pin "AC13") (pinfunction "P0.18/RESET_AC13") (pintype "bidirectional"))
    )
    (net (code "61") (name "SWDCLK") (class "Default")
      (node (ref "TP3") (pin "T") (pinfunction "T_T") (pintype "bidirectional"))
      (node (ref "U1") (pin "AA24") (pinfunction "SWDCLK_AA24") (pintype "input"))
    )
    (net (code "62") (name "SWDIO") (class "Default")
      (node (ref "TP5") (pin "T") (pinfunction "T_T") (pintype "bidirectional"))
      (node (ref "U1") (pin "AC24") (pinfunction "SWDIO_AC24") (pintype "bidirectional"))
    )
    (net (code "63") (name "USB_D+") (class "Default")
      (node (ref "R11") (pin "1") (pinfunction "1_1") (pintype "passive"))
      (node (ref "USB1") (pin "A6") (pinfunction "A6/DP1_A6") (pintype "bidirectional"))
      (node (ref "USB1") (pin "B6") (pinfunction "B6/DP2_B6") (pintype "bidirectional"))
    )
    (net (code "64") (name "USB_D-") (class "Default")
      (node (ref "R10") (pin "1") (pinfunction "1_1") (pintype "passive"))
      (node (ref "USB1") (pin "A7") (pinfunction "A7/DN1_A7") (pintype "bidirectional"))
      (node (ref "USB1") (pin "B7") (pinfunction "B7/DN2_B7") (pintype "bidirectional"))
    )
    (net (code "65") (name "VBAT") (class "Default")
      (node (ref "BAT") (pin "1") (pinfunction "T_1") (pintype "bidirectional"))
      (node (ref "C30") (pin "1") (pinfunction "1_1") (pintype "passive"))
      (node (ref "Q1") (pin "1") (pinfunction "D_1") (pintype "bidirectional"))
      (node (ref "R16") (pin "1") (pinfunction "1_1") (pintype "passive"))
      (node (ref "U2") (pin "A1") (pinfunction "OUT_A1") (pintype "bidirectional"))
    )
    (net (code "66") (name "VBUS") (class "Default")
      (node (ref "C25") (pin "2") (pinfunction "2_2") (pintype "passive"))
      (node (ref "C9") (pin "2") (pinfunction "2_2") (pintype "passive"))
      (node (ref "D1") (pin "+") (pinfunction "+_+") (pintype "passive"))
      (node (ref "J1") (pin "19") (pinfunction "7_19") (pintype "bidirectional"))
      (node (ref "J1") (pin "7") (pinfunction "7_7") (pintype "bidirectional"))
      (node (ref "Q1") (pin "2") (pinfunction "G_2") (pintype "bidirectional"))
      (node (ref "R9") (pin "2") (pinfunction "2_2") (pintype "passive"))
      (node (ref "U1") (pin "AD2") (pinfunction "VBUS_AD2") (pintype "bidirectional"))
      (node (ref "U2") (pin "A2") (pinfunction "IN_A2") (pintype "bidirectional"))
      (node (ref "USB1") (pin "A4_B9") (pinfunction "A4/B9/VBUS_A4_B9") (pintype "bidirectional"))
      (node (ref "USB1") (pin "B4_A9") (pinfunction "B4/A9/VBUS_B4_A9") (pintype "bidirectional"))
    )
    (net (code "67") (name "VIN") (class "Default")
      (node (ref "C4") (pin "1") (pinfunction "1_1") (pintype "passive"))
      (node (ref "D1") (pin "-") (pinfunction "-_-") (pintype "passive"))
      (node (ref "Q1") (pin "3") (pinfunction "S_3") (pintype "bidirectional"))
      (node (ref "U6") (pin "3") (pinfunction "EN_3") (pintype "bidirectional"))
      (node (ref "U6") (pin "4") (pinfunction "IN_4") (pintype "bidirectional"))
    )
    (net (code "68") (name "unconnected-(U1-DCCH-PadAB2)") (class "Default")
      (node (ref "U1") (pin "AB2") (pinfunction "DCCH_AB2") (pintype "bidirectional"))
    )
    (net (code "69") (name "unconnected-(U1-P0.08-PadN1)") (class "Default")
      (node (ref "U1") (pin "N1") (pinfunction "P0.08_N1") (pintype "bidirectional"))
    )
    (net (code "70") (name "unconnected-(U1-P0.12-PadU1)") (class "Default")
      (node (ref "U1") (pin "U1") (pinfunction "P0.12_U1") (pintype "bidirectional"))
    )
    (net (code "71") (name "unconnected-(U1-P0.15-PadAD10)") (class "Default")
      (node (ref "U1") (pin "AD10") (pinfunction "P0.15_AD10") (pintype "bidirectional"))
    )
    (net (code "72") (name "unconnected-(U1-P0.19-PadAC15)") (class "Default")
      (node (ref "U1") (pin "AC15") (pinfunction "P0.19_AC15") (pintype "bidirectional"))
    )
    (net (code "73") (name "unconnected-(U1-P1.01-PadY23)") (class "Default")
      (node (ref "U1") (pin "Y23") (pinfunction "P1.01_Y23") (pintype "bidirectional"))
    )
    (net (code "74") (name "unconnected-(U1-P1.02-PadW24)") (class "Default")
      (node (ref "U1") (pin "W24") (pinfunction "P1.02_W24") (pintype "bidirectional"))
    )
    (net (code "75") (name "unconnected-(U1-P1.03-PadV23)") (class "Default")
      (node (ref "U1") (pin "V23") (pinfunction "P1.03_V23") (pintype "bidirectional"))
    )
    (net (code "76") (name "unconnected-(U1-P1.04-PadU24)") (class "Default")
      (node (ref "U1") (pin "U24") (pinfunction "P1.04_U24") (pintype "bidirectional"))
    )
    (net (code "77") (name "unconnected-(U1-P1.05-PadT23)") (class "Default")
      (node (ref "U1") (pin "T23") (pinfunction "P1.05_T23") (pintype "bidirectional"))
    )
    (net (code "78") (name "unconnected-(U1-P1.07-PadP23)") (class "Default")
      (node (ref "U1") (pin "P23") (pinfunction "P1.07_P23") (pintype "bidirectional"))
    )
    (net (code "79") (name "unconnected-(U1-P1.09-PadR1)") (class "Default")
      (node (ref "U1") (pin "R1") (pinfunction "P1.09_R1") (pintype "bidirectional"))
    )
    (net (code "80") (name "unconnected-(U3-INT2-Pad9)") (class "Default")
      (node (ref "U3") (pin "9") (pinfunction "INT2_9") (pintype "bidirectional"))
    )
    (net (code "81") (name "unconnected-(U3-NC-Pad10)") (class "Default")
      (node (ref "U3") (pin "10") (pinfunction "NC_10") (pintype "bidirectional"))
    )
    (net (code "82") (name "unconnected-(U3-NC-Pad11)") (class "Default")
      (node (ref "U3") (pin "11") (pinfunction "NC_11") (pintype "bidirectional"))
    )
    (net (code "83") (name "unconnected-(USB1-A8{slash}SBU1-PadA8)") (class "Default")
      (node (ref "USB1") (pin "A8") (pinfunction "A8/SBU1_A8") (pintype "bidirectional"))
    )
    (net (code "84") (name "unconnected-(USB1-B8{slash}SBU2-PadB8)") (class "Default")
      (node (ref "USB1") (pin "B8") (pinfunction "B8/SBU2_B8") (pintype "bidirectional"))
    )
    (net (code "85") (name "{slash}CE") (class "Default")
      (node (ref "R20") (pin "1") (pinfunction "1_1") (pintype "passive"))
      (node (ref "U2") (pin "B1") (pinfunction "TS_B1") (pintype "bidirectional"))
    )
  )
)
